# button.net
KiCad netlist of a schematic drawn in Altium Designer
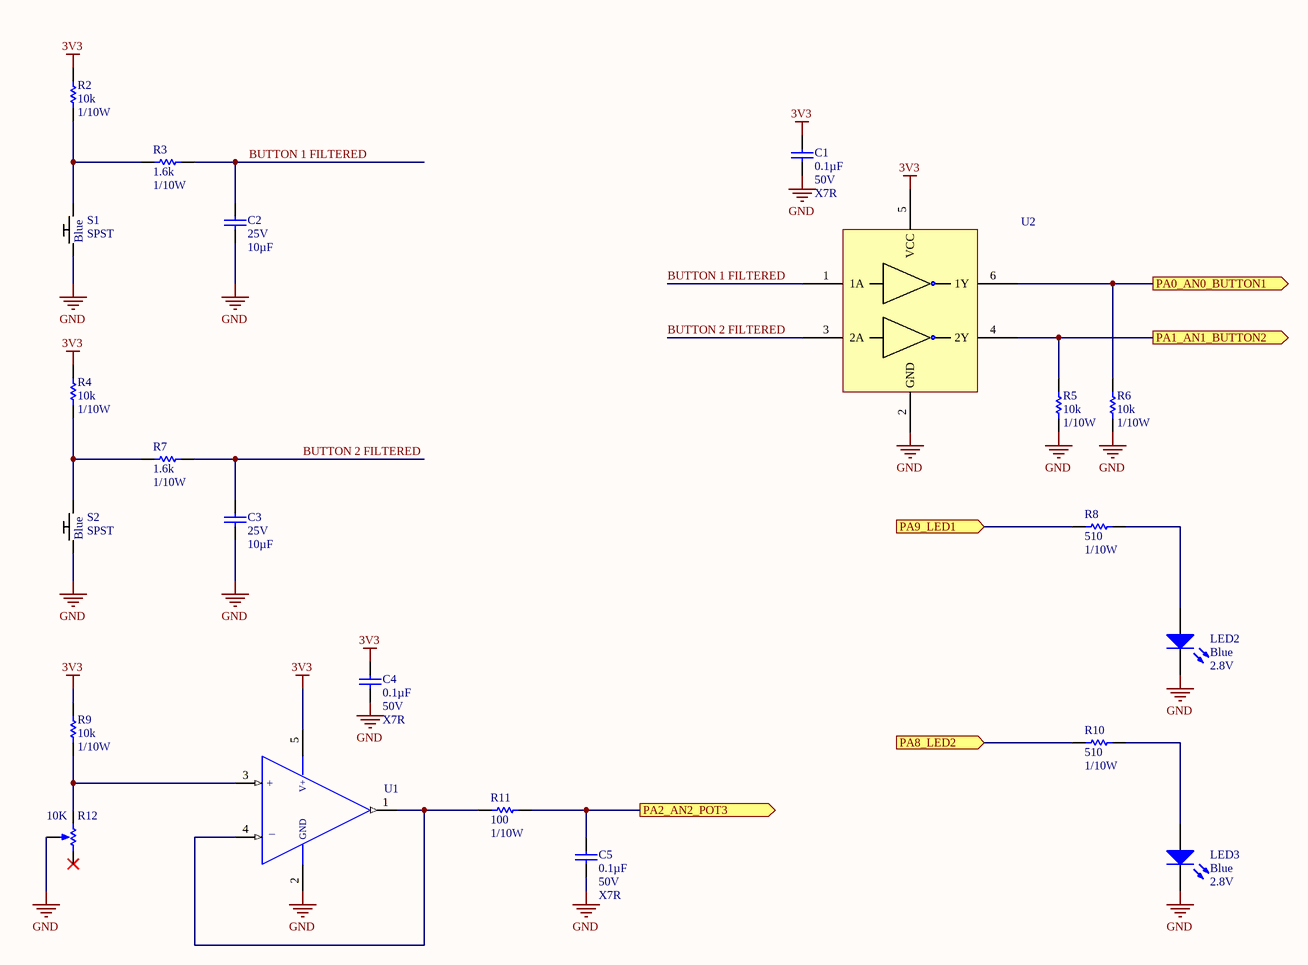
[diagram p0: button.SchDoc]

(export (version "E")
  (design (tool "Eeschema 10.0.6"))
  (components
    (comp (ref "C1")
      (value "CAP CER 0.1UF 50V 10% X7R 0603")
      (footprint "CAP, 0603")
      (description "0.10µF ±10% 50V Ceramic Capacitor X7R 0603 (1608 Metric)")
      (fields
        (field (name "TOLERANCE") "±10%")
        (field (name "CAPACITANCE") "0.1µF")
        (field (name "VOLTAGE") "50V")
        (field (name "TEMPERATURE COEFFICIENT") "X7R")
      )
      (libsource (lib "Schematic Diagrams") (part "CAP CER 0.1UF 50V 10% X7R 0603"))
    )
    (comp (ref "C2")
      (value "CAP CER 10uF 25V 10% X5R 0805")
      (footprint "CAP, 0805")
      (description "10µF ±10% 25V Ceramic Capacitor X5R 0805 (2012 Metric)")
      (fields
        (field (name "MANUFACTURER") "Murata Electronics North America")
        (field (name "MANUFACTURER PART NUMBER") "GRM21BR61E106KA73L")
        (field (name "VOLTAGE - RATED") "25V")
        (field (name "CAPACITANCE") "10µF")
      )
      (libsource (lib "Schematic Diagrams") (part "CAP CER 10uF 25V 10% X5R 0805"))
    )
    (comp (ref "C3")
      (value "CAP CER 10uF 25V 10% X5R 0805")
      (footprint "CAP, 0805")
      (description "10µF ±10% 25V Ceramic Capacitor X5R 0805 (2012 Metric)")
      (fields
        (field (name "MANUFACTURER") "Murata Electronics North America")
        (field (name "MANUFACTURER PART NUMBER") "GRM21BR61E106KA73L")
        (field (name "VOLTAGE - RATED") "25V")
        (field (name "CAPACITANCE") "10µF")
      )
      (libsource (lib "Schematic Diagrams") (part "CAP CER 10uF 25V 10% X5R 0805"))
    )
    (comp (ref "C4")
      (value "CAP CER 0.1UF 50V 10% X7R 0603")
      (footprint "CAP, 0603")
      (description "0.10µF ±10% 50V Ceramic Capacitor X7R 0603 (1608 Metric)")
      (fields
        (field (name "TOLERANCE") "±10%")
        (field (name "CAPACITANCE") "0.1µF")
        (field (name "VOLTAGE") "50V")
        (field (name "TEMPERATURE COEFFICIENT") "X7R")
      )
      (libsource (lib "Schematic Diagrams") (part "CAP CER 0.1UF 50V 10% X7R 0603"))
    )
    (comp (ref "C5")
      (value "CAP CER 0.1UF 50V 10% X7R 0603")
      (footprint "CAP, 0603")
      (description "0.10µF ±10% 50V Ceramic Capacitor X7R 0603 (1608 Metric)")
      (fields
        (field (name "TOLERANCE") "±10%")
        (field (name "CAPACITANCE") "0.1µF")
        (field (name "VOLTAGE") "50V")
        (field (name "TEMPERATURE COEFFICIENT") "X7R")
      )
      (libsource (lib "Schematic Diagrams") (part "CAP CER 0.1UF 50V 10% X7R 0603"))
    )
    (comp (ref "LED2")
      (value "LED BLUE CLEAR 2.8V 0603")
      (footprint "LED_0603")
      (description "Blue 470nm LED Indication - Discrete 2.8V 0603 (1608 Metric)")
      (fields (field (name "COLOR") "Blue") (field (name "VOLTAGE - FORWARD (VF) (TYP)") "2.8V"))
      (libsource (lib "Schematic Diagrams") (part "LED BLUE CLEAR 2.8V 0603"))
    )
    (comp (ref "LED3")
      (value "LED BLUE CLEAR 2.8V 0603")
      (footprint "LED_0603")
      (description "Blue 470nm LED Indication - Discrete 2.8V 0603 (1608 Metric)")
      (fields (field (name "COLOR") "Blue") (field (name "VOLTAGE - FORWARD (VF) (TYP)") "2.8V"))
      (libsource (lib "Schematic Diagrams") (part "LED BLUE CLEAR 2.8V 0603"))
    )
    (comp (ref "R2")
      (value "RES 10K OHM 1% 1/10W 0603")
      (footprint "RES, 0603")
      (description "RES SMD 10K OHM 1% 1/10W 0603")
      (fields
        (field (name "TOLERANCE") "±1%")
        (field (name "RESISTANCE") "10k")
        (field (name "POWER") "1/10W")
      )
      (libsource (lib "Schematic Diagrams") (part "RES 10K OHM 1% 1/10W 0603"))
    )
    (comp (ref "R3")
      (value "RES 1.6K OHM 1% 1/10W 0603")
      (footprint "RES, 0603")
      (description "1.6 kOhms ±1% 0.1W, 1/10W Chip Resistor 0603 (1608 Metric) Moisture Resistant Thick Film")
      (fields
        (field (name "MANUFACTURER") "Yageo")
        (field (name "MANUFACTURER PART NUMBER") "RC0603FR-071K6L")
        (field (name "RESISTANCE") "1.6k")
        (field (name "POWER RATING") "1/10W")
      )
      (libsource (lib "Schematic Diagrams") (part "RES 1.6K OHM 1% 1/10W 0603"))
    )
    (comp (ref "R4")
      (value "RES 10K OHM 1% 1/10W 0603")
      (footprint "RES, 0603")
      (description "RES SMD 10K OHM 1% 1/10W 0603")
      (fields
        (field (name "TOLERANCE") "±1%")
        (field (name "RESISTANCE") "10k")
        (field (name "POWER") "1/10W")
      )
      (libsource (lib "Schematic Diagrams") (part "RES 10K OHM 1% 1/10W 0603"))
    )
    (comp (ref "R5")
      (value "RES 10K OHM 1% 1/10W 0603")
      (footprint "RES, 0603")
      (description "RES SMD 10K OHM 1% 1/10W 0603")
      (fields
        (field (name "TOLERANCE") "±1%")
        (field (name "RESISTANCE") "10k")
        (field (name "POWER") "1/10W")
      )
      (libsource (lib "Schematic Diagrams") (part "RES 10K OHM 1% 1/10W 0603"))
    )
    (comp (ref "R6")
      (value "RES 10K OHM 1% 1/10W 0603")
      (footprint "RES, 0603")
      (description "RES SMD 10K OHM 1% 1/10W 0603")
      (fields
        (field (name "TOLERANCE") "±1%")
        (field (name "RESISTANCE") "10k")
        (field (name "POWER") "1/10W")
      )
      (libsource (lib "Schematic Diagrams") (part "RES 10K OHM 1% 1/10W 0603"))
    )
    (comp (ref "R7")
      (value "RES 1.6K OHM 1% 1/10W 0603")
      (footprint "RES, 0603")
      (description "1.6 kOhms ±1% 0.1W, 1/10W Chip Resistor 0603 (1608 Metric) Moisture Resistant Thick Film")
      (fields
        (field (name "MANUFACTURER") "Yageo")
        (field (name "MANUFACTURER PART NUMBER") "RC0603FR-071K6L")
        (field (name "RESISTANCE") "1.6k")
        (field (name "POWER RATING") "1/10W")
      )
      (libsource (lib "Schematic Diagrams") (part "RES 1.6K OHM 1% 1/10W 0603"))
    )
    (comp (ref "R8")
      (value "RES 510 OHM 5% 1/10W 0603")
      (footprint "RES, 0603")
      (description "RES SMD 510 OHM 5% 1/10W 0603")
      (fields
        (field (name "TOLERANCE") "±5%")
        (field (name "RESISTANCE") "510")
        (field (name "POWER") "1/10W")
      )
      (libsource (lib "Schematic Diagrams") (part "RES 510 OHM 5% 1/10W 0603"))
    )
    (comp (ref "R9")
      (value "RES 10K OHM 1% 1/10W 0603")
      (footprint "RES, 0603")
      (description "RES SMD 10K OHM 1% 1/10W 0603")
      (fields
        (field (name "TOLERANCE") "±1%")
        (field (name "RESISTANCE") "10k")
        (field (name "POWER") "1/10W")
      )
      (libsource (lib "Schematic Diagrams") (part "RES 10K OHM 1% 1/10W 0603"))
    )
    (comp (ref "R10")
      (value "RES 510 OHM 5% 1/10W 0603")
      (footprint "RES, 0603")
      (description "RES SMD 510 OHM 5% 1/10W 0603")
      (fields
        (field (name "TOLERANCE") "±5%")
        (field (name "RESISTANCE") "510")
        (field (name "POWER") "1/10W")
      )
      (libsource (lib "Schematic Diagrams") (part "RES 510 OHM 5% 1/10W 0603"))
    )
    (comp (ref "R11")
      (value "RES 100 OHM 1% 1/10W 0603")
      (footprint "RES, 0603")
      (description "100 Ohm ±1% 0.1W, 1/10W Chip Resistor 0603 (1608 Metric) Moisture Resistant Thick Film")
      (fields
        (field (name "TOLERANCE") "±1%")
        (field (name "RESISTANCE") "100")
        (field (name "POWER") "1/10W")
      )
      (libsource (lib "Schematic Diagrams") (part "RES 100 OHM 1% 1/10W 0603"))
    )
    (comp (ref "R12")
      (value "POT 10K OHM LINEAR THROUGH HOLE")
      (footprint "POT 10K OHM LINEAR THROUGH HOLE")
      (fields (field (name "TOLERANCE") "20%"))
      (libsource (lib "Schematic Diagrams") (part "POT 10K OHM LINEAR THROUGH HOLE"))
    )
    (comp (ref "S1")
      (value "SPST")
      (footprint "SW SPST D6 SERIES BLUE")
      (description "Pushbutton Switch SPST-NO Keyswitch Through Hole D6 Series Blue")
      (fields (field (name "MANUFACTURER") "C&K") (field (name "MANUFACTURER PART NUMBER") "D6R60 F1 LFS"))
      (libsource (lib "Schematic Diagrams") (part "SW SPST-NO 0.1A 32V D6 Series Blue"))
    )
    (comp (ref "S2")
      (value "SPST")
      (footprint "SW SPST D6 SERIES BLUE")
      (description "Pushbutton Switch SPST-NO Keyswitch Through Hole D6 Series Blue")
      (fields (field (name "MANUFACTURER") "C&K") (field (name "MANUFACTURER PART NUMBER") "D6R60 F1 LFS"))
      (libsource (lib "Schematic Diagrams") (part "SW SPST-NO 0.1A 32V D6 Series Blue"))
    )
    (comp (ref "U1")
      (value "IC OP AMP GEN PURPOSE RR 10MHZ SOT-23-5")
      (footprint "IC OP AMP GP RR 10MHZ SOT-23-5")
      (description "General Purpose Amplifier 1 Circuit Rail-to-Rail SOT-23-5")
      (libsource (lib "Schematic Diagrams") (part "IC OP AMP GEN PURPOSE RR 10MHZ SOT-23-5"))
    )
    (comp (ref "U2")
      (value "IC INVERTER SCHMITT 2CH 6-TSSOP")
      (footprint "SOT363")
      (description "2CH 6-TSSOP")
      (libsource (lib "Schematic Diagrams") (part "IC INVERTER SCHMITT 2CH 6-TSSOP"))
    )
  )
  (nets
    (net (code "1") (name "/BUTTON 1 FILTERED") (class "Default")
      (node (ref "C2") (pin "1") (pinfunction "1_1") (pintype "passive"))
      (node (ref "R3") (pin "2") (pinfunction "2_2") (pintype "passive"))
      (node (ref "U2") (pin "1") (pinfunction "1A_1") (pintype "passive"))
    )
    (net (code "2") (name "/BUTTON 2 FILTERED") (class "Default")
      (node (ref "C3") (pin "1") (pinfunction "1_1") (pintype "passive"))
      (node (ref "R7") (pin "2") (pinfunction "2_2") (pintype "passive"))
      (node (ref "U2") (pin "3") (pinfunction "2A_3") (pintype "passive"))
    )
    (net (code "3") (name "/PA0_AN0_BUTTON1") (class "Default")
      (node (ref "R6") (pin "1") (pinfunction "1_1") (pintype "passive"))
      (node (ref "U2") (pin "6") (pinfunction "1Y_6") (pintype "passive"))
    )
    (net (code "4") (name "/PA1_AN1_BUTTON2") (class "Default")
      (node (ref "R5") (pin "1") (pinfunction "1_1") (pintype "passive"))
      (node (ref "U2") (pin "4") (pinfunction "2Y_4") (pintype "passive"))
    )
    (net (code "5") (name "/PA2_AN2_POT3") (class "Default")
      (node (ref "C5") (pin "1") (pinfunction "1_1") (pintype "passive"))
      (node (ref "R11") (pin "2") (pinfunction "2_2") (pintype "passive"))
    )
    (net (code "6") (name "/PA8_LED2") (class "Default")
      (node (ref "R10") (pin "1") (pinfunction "1_1") (pintype "passive"))
    )
    (net (code "7") (name "/PA9_LED1") (class "Default")
      (node (ref "R8") (pin "1") (pinfunction "1_1") (pintype "passive"))
    )
    (net (code "8") (name "3V3") (class "Default")
      (node (ref "C1") (pin "1") (pinfunction "1_1") (pintype "passive"))
      (node (ref "C4") (pin "1") (pinfunction "1_1") (pintype "passive"))
      (node (ref "R2") (pin "1") (pinfunction "1_1") (pintype "passive"))
      (node (ref "R4") (pin "1") (pinfunction "1_1") (pintype "passive"))
      (node (ref "R9") (pin "1") (pinfunction "1_1") (pintype "passive"))
      (node (ref "U1") (pin "5") (pinfunction "VDD_5") (pintype "power_in"))
      (node (ref "U2") (pin "5") (pinfunction "VCC_5") (pintype "passive"))
    )
    (net (code "9") (name "GND") (class "Default")
      (node (ref "C1") (pin "2") (pinfunction "2_2") (pintype "passive"))
      (node (ref "C2") (pin "2") (pinfunction "2_2") (pintype "passive"))
      (node (ref "C3") (pin "2") (pinfunction "2_2") (pintype "passive"))
      (node (ref "C4") (pin "2") (pinfunction "2_2") (pintype "passive"))
      (node (ref "C5") (pin "2") (pinfunction "2_2") (pintype "passive"))
      (node (ref "LED2") (pin "2") (pinfunction "K_2") (pintype "passive"))
      (node (ref "LED3") (pin "2") (pinfunction "K_2") (pintype "passive"))
      (node (ref "R12") (pin "2") (pinfunction "TAP_2") (pintype "passive"))
      (node (ref "R5") (pin "2") (pinfunction "2_2") (pintype "passive"))
      (node (ref "R6") (pin "2") (pinfunction "2_2") (pintype "passive"))
      (node (ref "S1") (pin "1") (pinfunction "1_1") (pintype "passive"))
      (node (ref "S2") (pin "1") (pinfunction "1_1") (pintype "passive"))
      (node (ref "U1") (pin "2") (pinfunction "VSS_2") (pintype "power_in"))
      (node (ref "U2") (pin "2") (pinfunction "GND_2") (pintype "passive"))
    )
    (net (code "10") (name "Net-(LED2-A)") (class "Default")
      (node (ref "LED2") (pin "1") (pinfunction "A_1") (pintype "passive"))
      (node (ref "R8") (pin "2") (pinfunction "2_2") (pintype "passive"))
    )
    (net (code "11") (name "Net-(LED3-A)") (class "Default")
      (node (ref "LED3") (pin "1") (pinfunction "A_1") (pintype "passive"))
      (node (ref "R10") (pin "2") (pinfunction "2_2") (pintype "passive"))
    )
    (net (code "12") (name "Net-(R2-Pad2)") (class "Default")
      (node (ref "R2") (pin "2") (pinfunction "2_2") (pintype "passive"))
      (node (ref "R3") (pin "1") (pinfunction "1_1") (pintype "passive"))
      (node (ref "S1") (pin "2") (pinfunction "2_2") (pintype "passive"))
    )
    (net (code "13") (name "Net-(R4-Pad2)") (class "Default")
      (node (ref "R4") (pin "2") (pinfunction "2_2") (pintype "passive"))
      (node (ref "R7") (pin "1") (pinfunction "1_1") (pintype "passive"))
      (node (ref "S2") (pin "2") (pinfunction "2_2") (pintype "passive"))
    )
    (net (code "14") (name "Net-(R12-TOP)") (class "Default")
      (node (ref "R12") (pin "1") (pinfunction "TOP_1") (pintype "passive"))
      (node (ref "R9") (pin "2") (pinfunction "2_2") (pintype "passive"))
      (node (ref "U1") (pin "3") (pinfunction "+IN_3") (pintype "input"))
    )
    (net (code "15") (name "Net-(U1--IN)") (class "Default")
      (node (ref "R11") (pin "1") (pinfunction "1_1") (pintype "passive"))
      (node (ref "U1") (pin "1") (pinfunction "OUTPUT_1") (pintype "output"))
      (node (ref "U1") (pin "4") (pinfunction "-IN_4") (pintype "input"))
    )
    (net (code "16") (name "unconnected-(R12-BOT-Pad3)") (class "Default")
      (node (ref "R12") (pin "3") (pinfunction "BOT_3") (pintype "passive+no_connect"))
    )
  )
)
